# SCH_Nucleo__LCD__v5_2023-10-04.net
KiCad netlist of a schematic drawn in EasyEDA
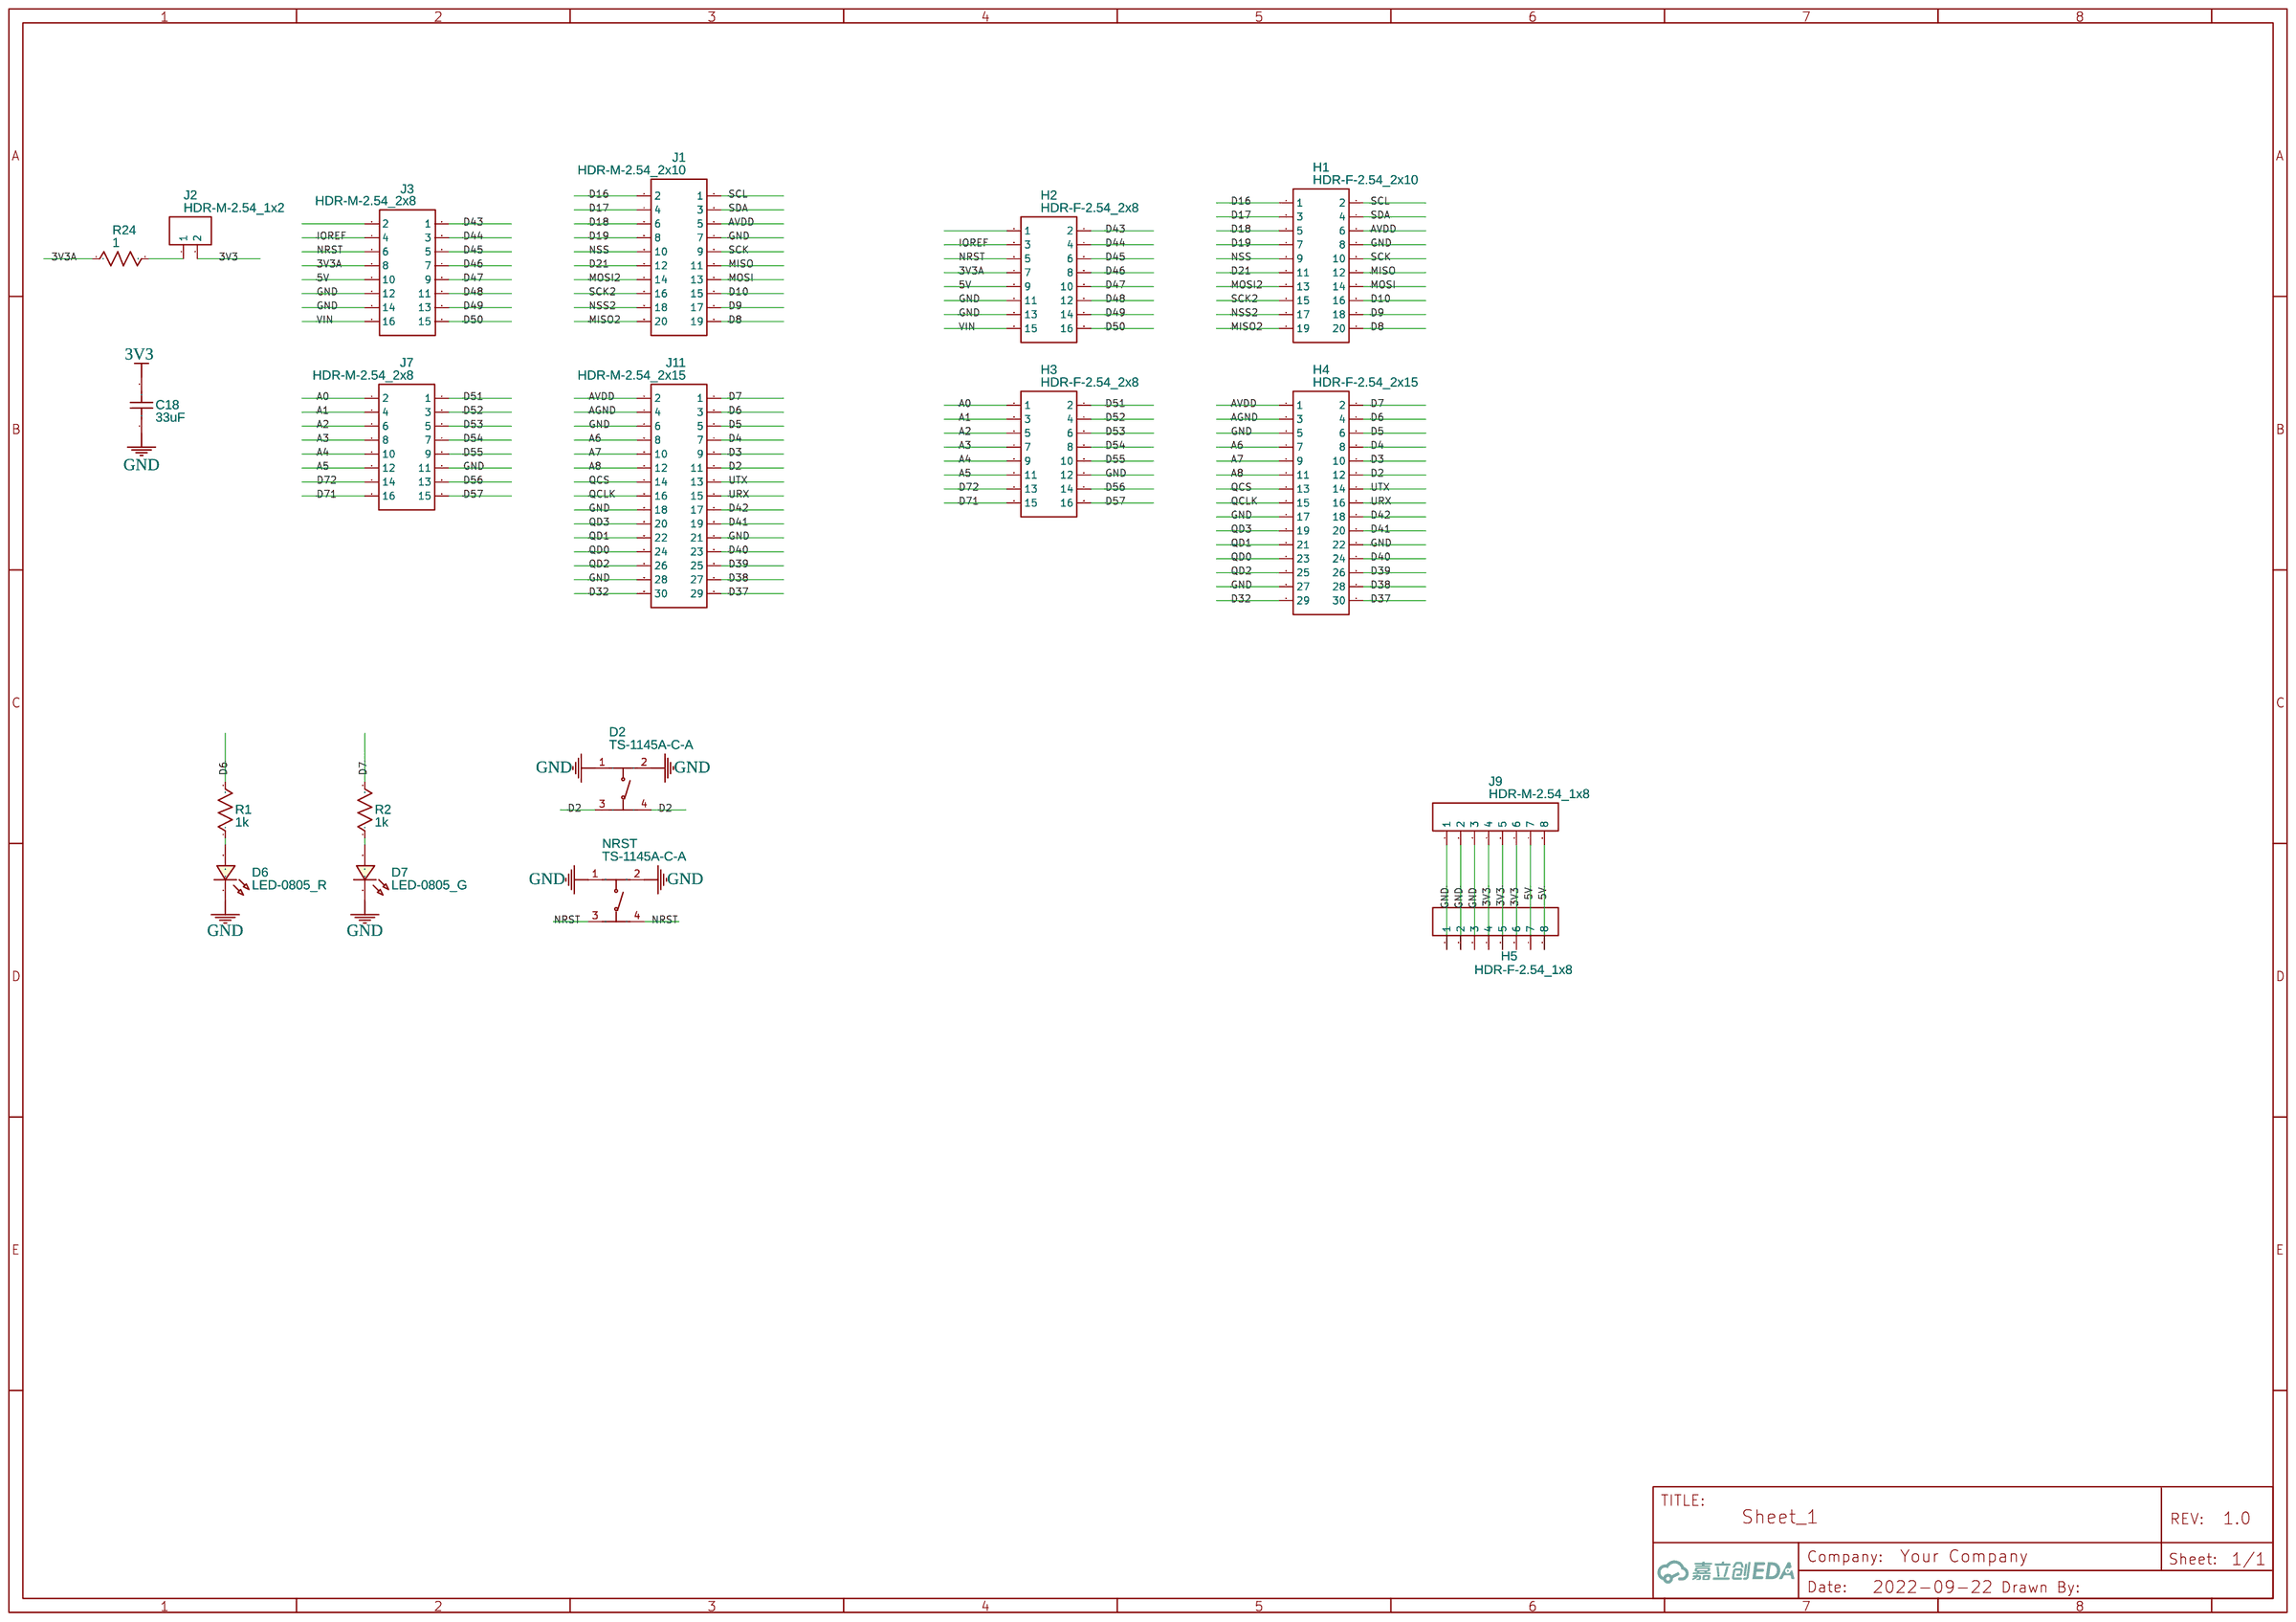
[diagram p0: 连接器]
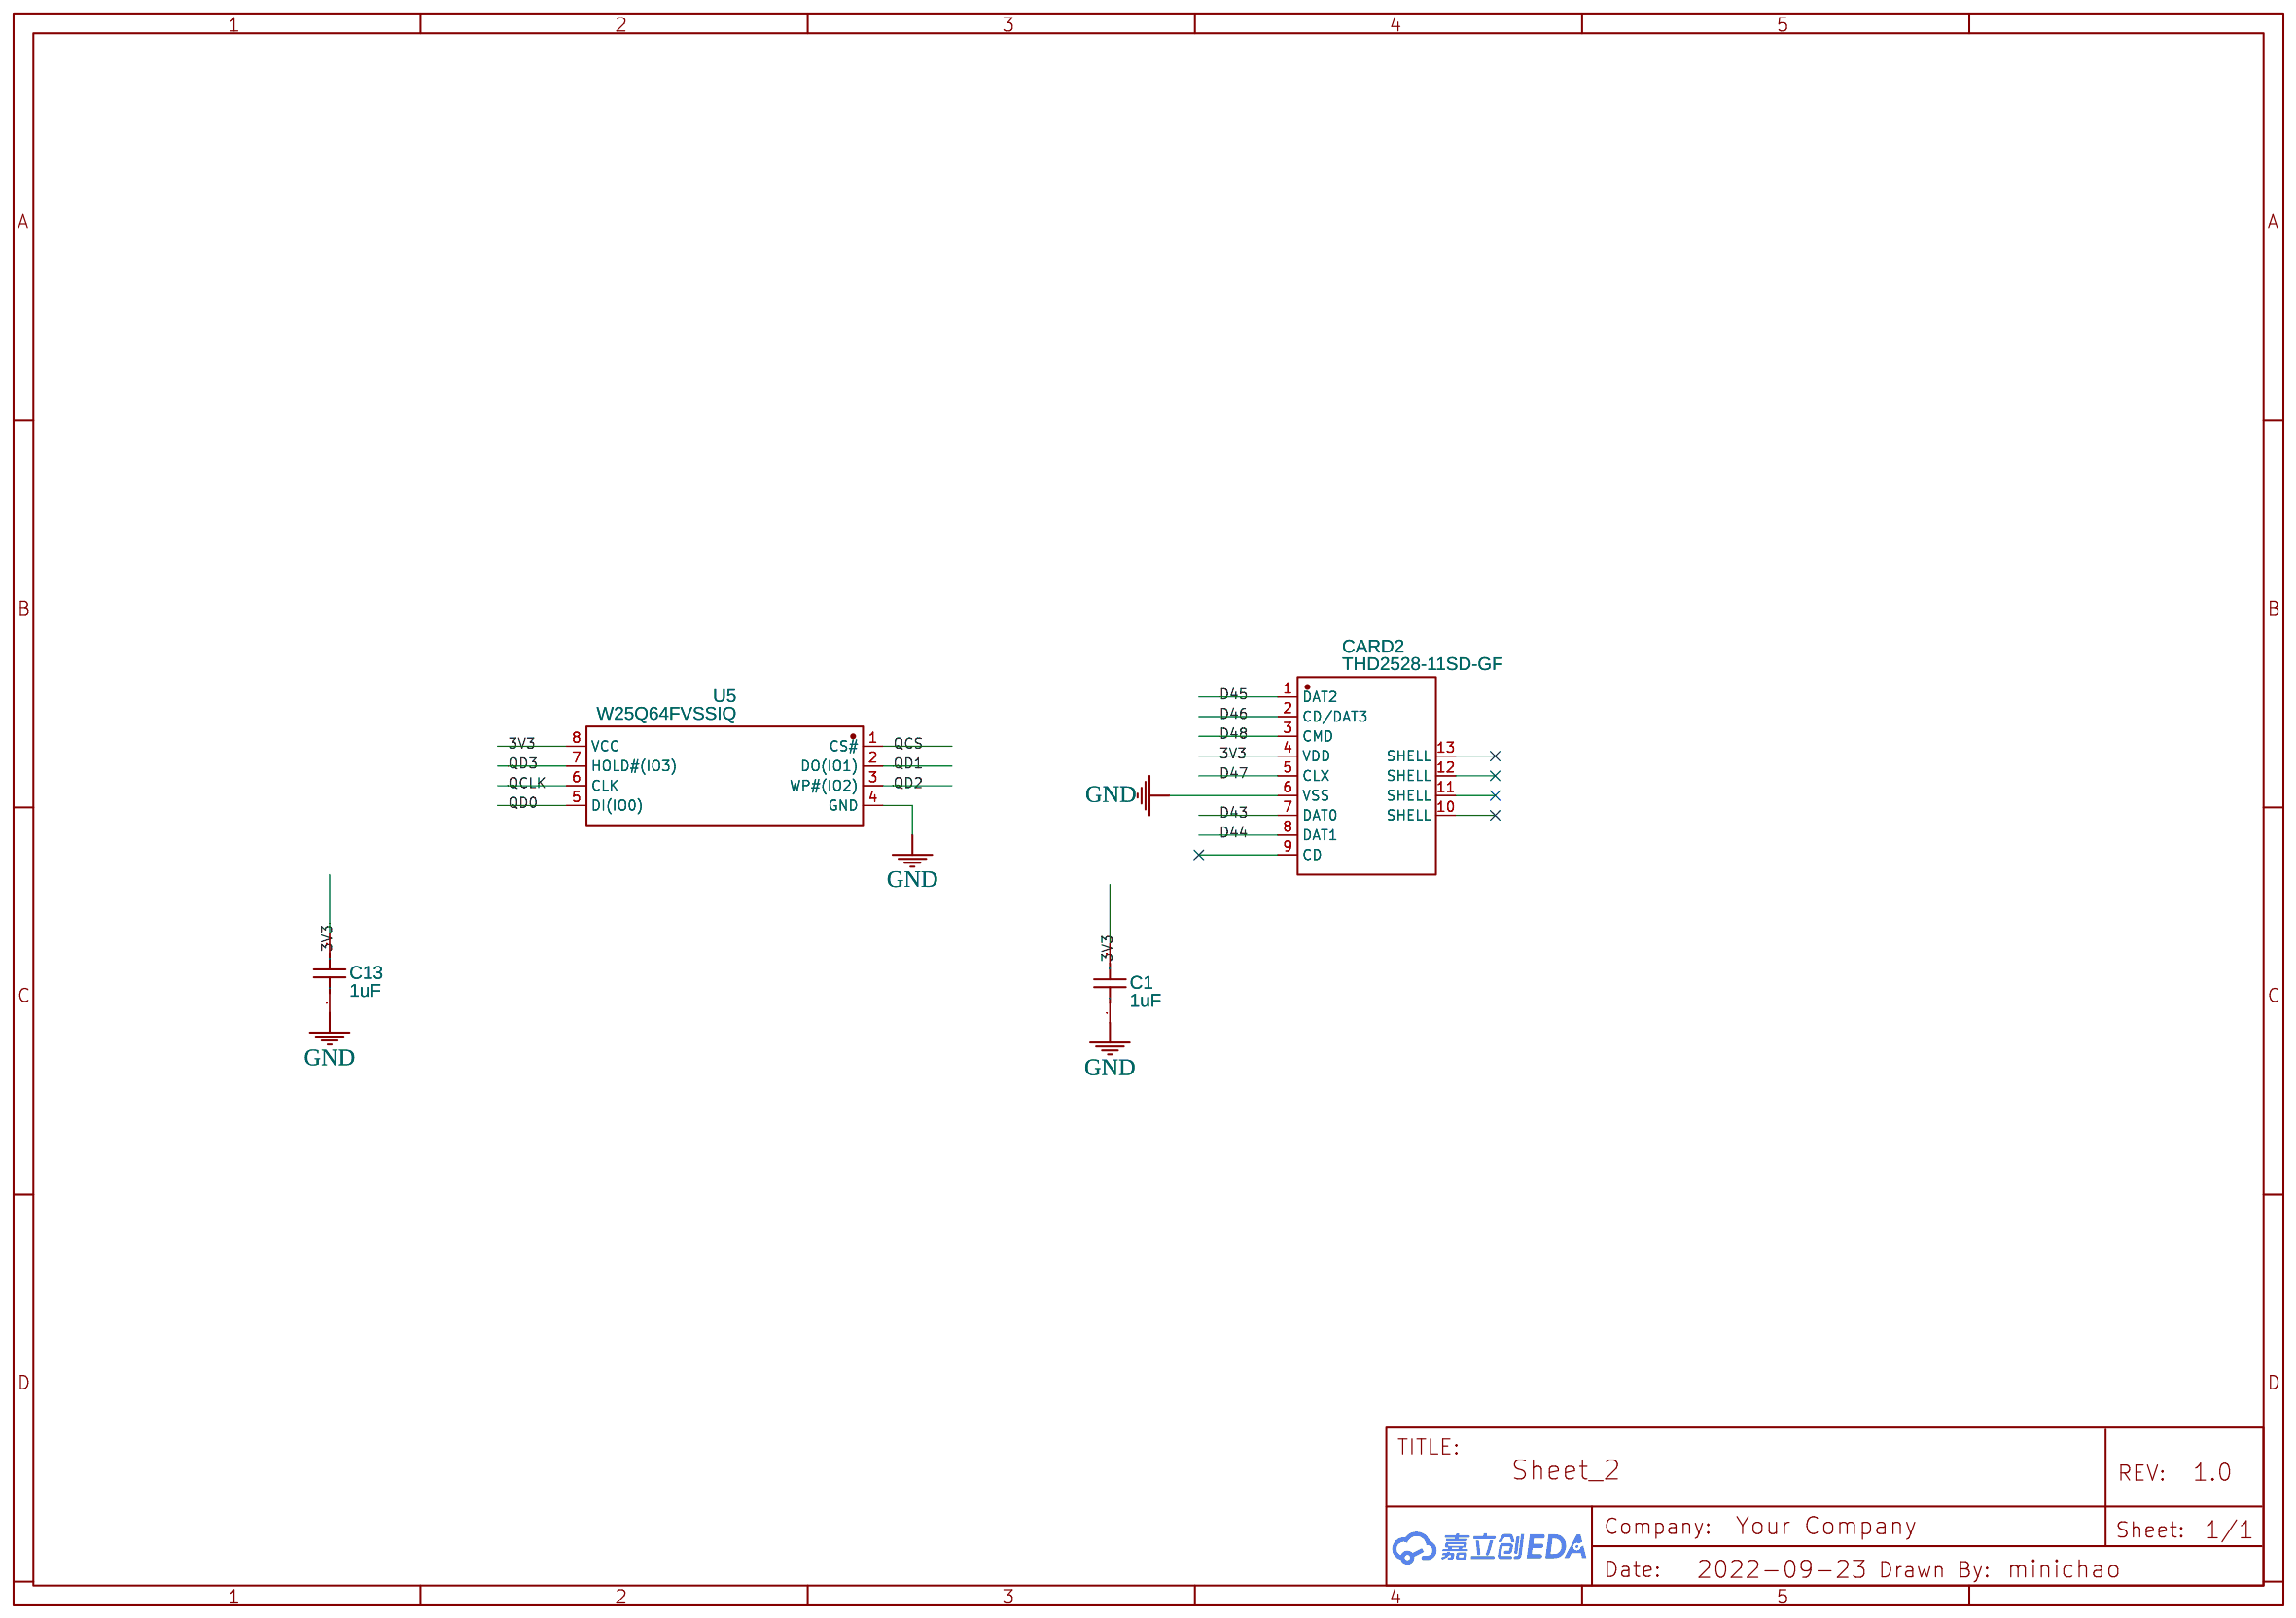
[diagram p1: 存储]
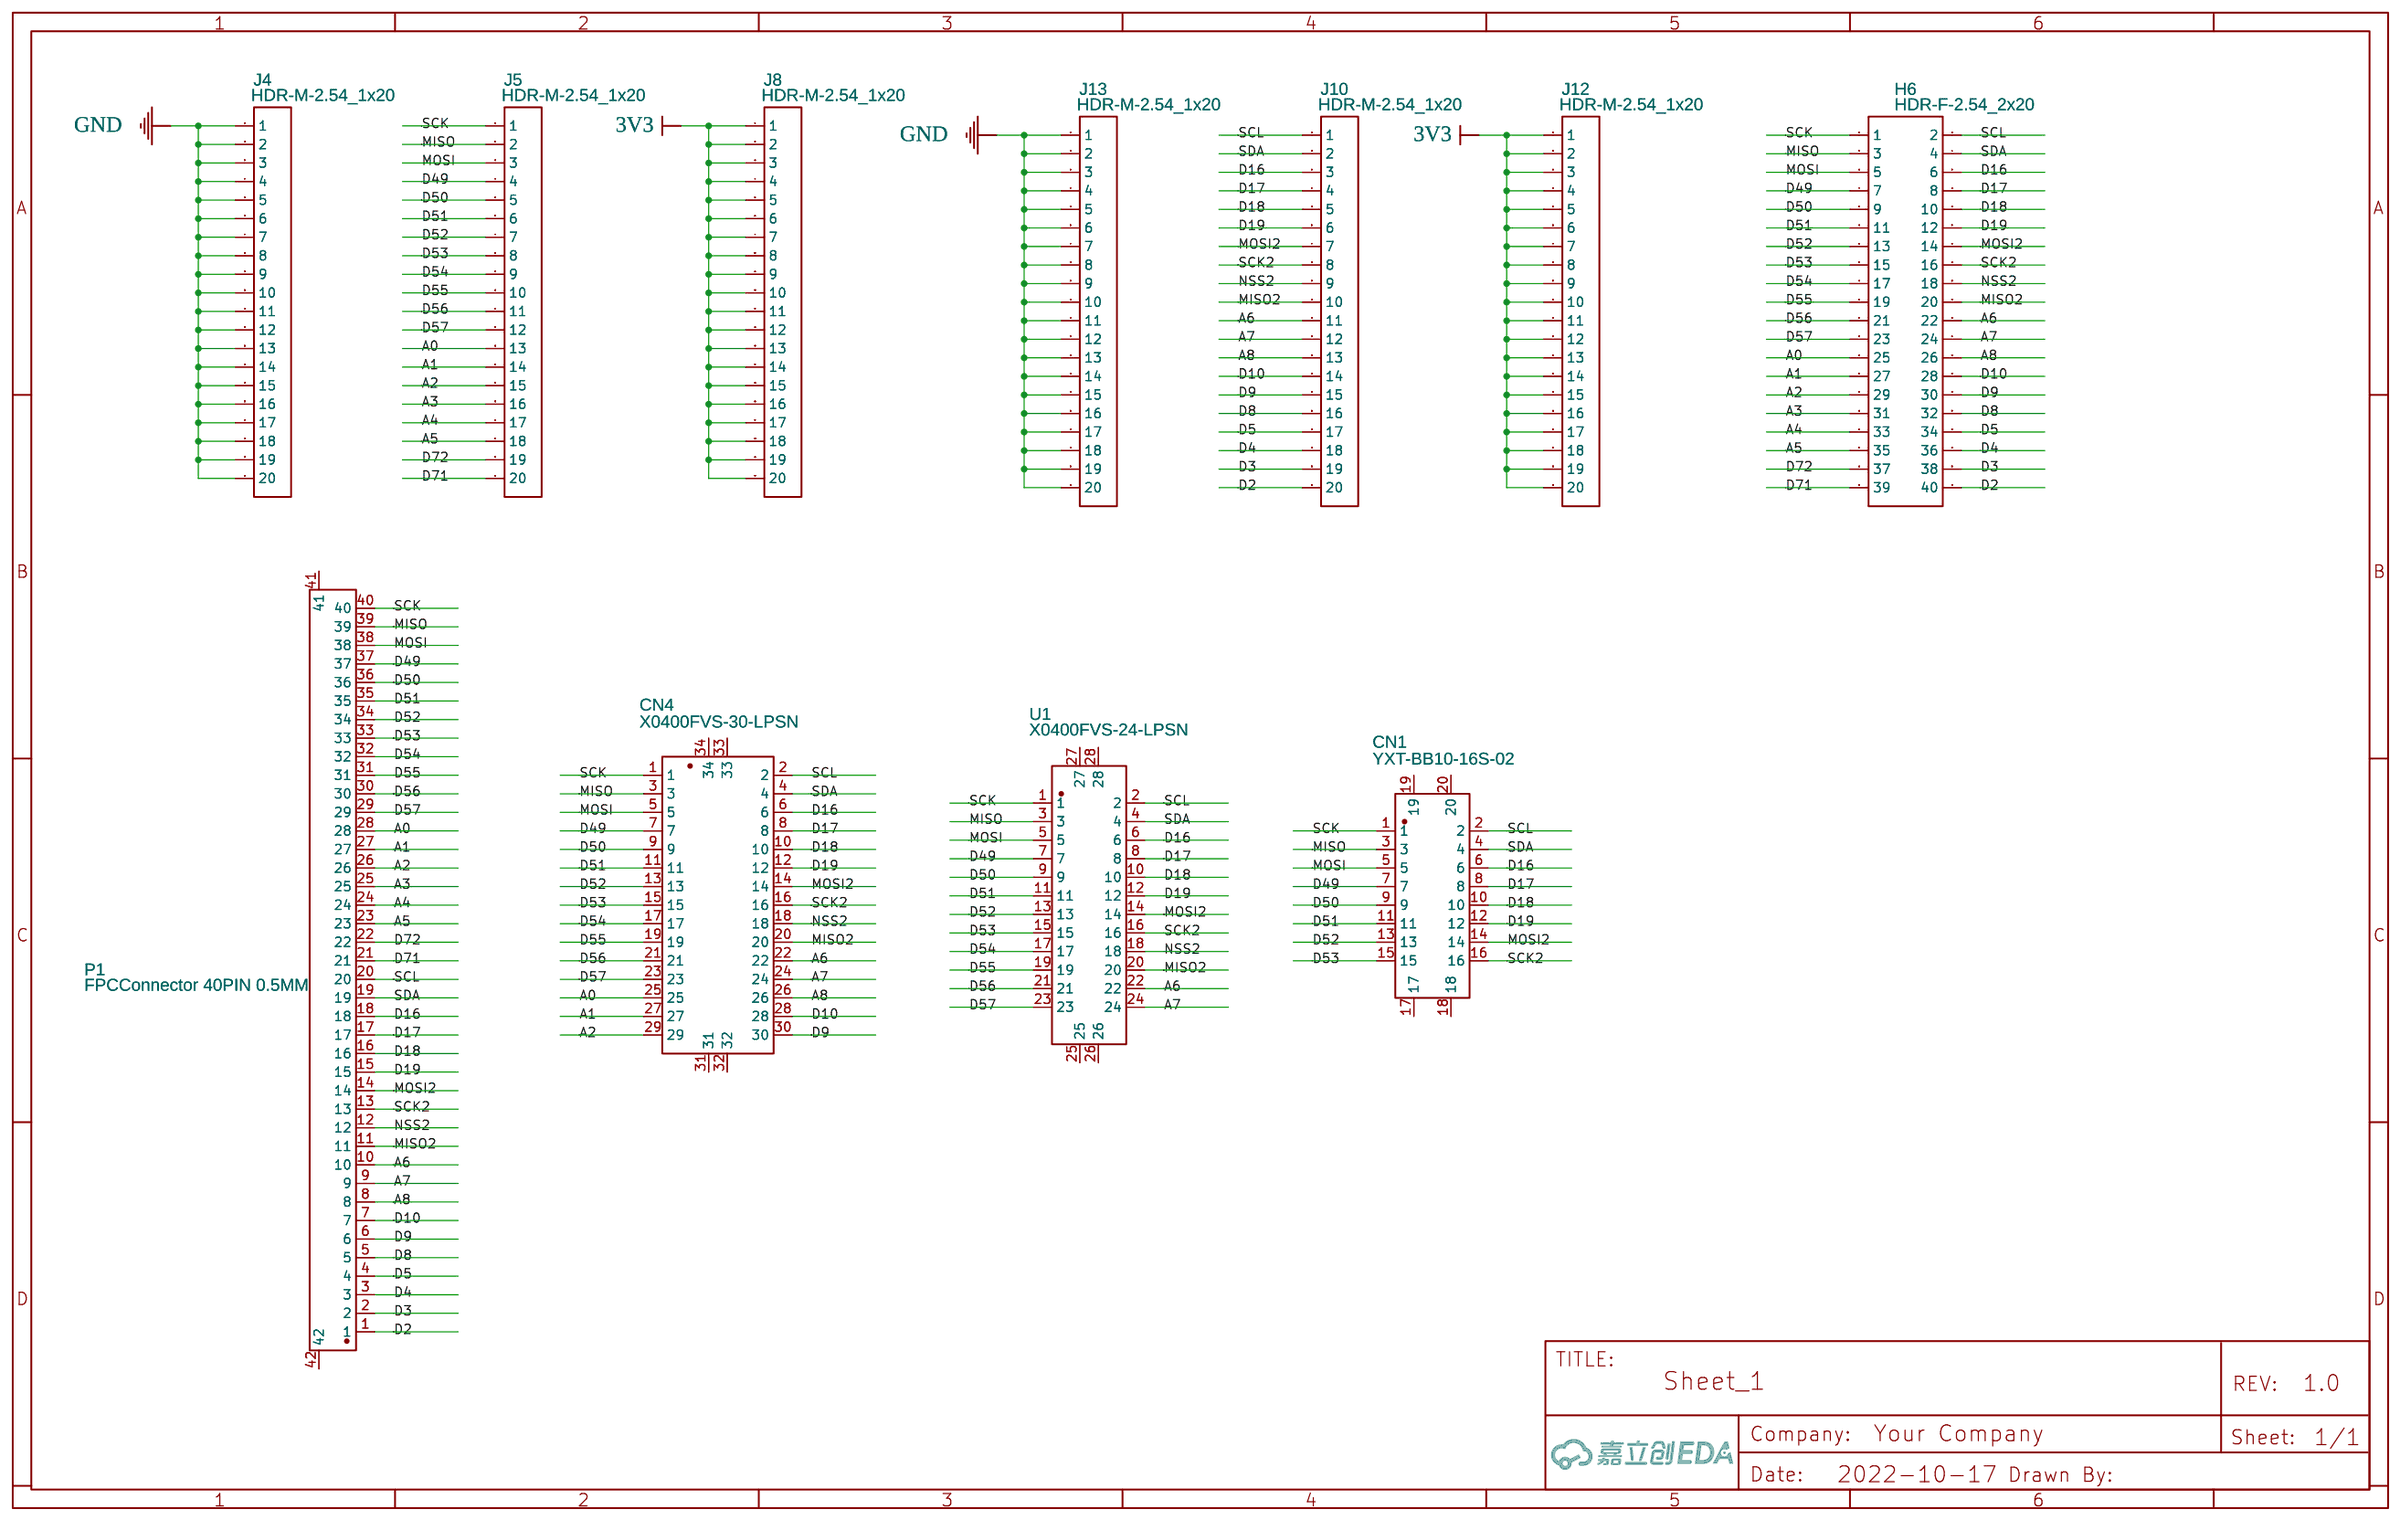
[diagram p2: 显示]

(export (version "E")
  (design (tool "Eeschema 10.0.6"))
  (components
    (comp (ref "C18")
      (value "33uF")
      (fields
        (field (name "BOM_Manufacturer Part") "C3225X5R0J336MT0A0N")
        (field (name "BOM_Supplier Part") "C695362")
      )
      (libsource (lib "") (part "C3225X5R0J336MT0A0N"))
    )
    (comp (ref "D2")
      (value "TS-1145A-C-A")
      (fields (field (name "BOM_Supplier Part") "C318903"))
      (libsource (lib "") (part "TS-1145A-C-A_1"))
    )
    (comp (ref "D6")
      (value "LED-0805_R")
      (fields
        (field (name "BOM_Manufacturer Part") "17-21SURC/S530-A3/TR8")
        (field (name "BOM_Supplier Part") "C72037")
      )
      (libsource (lib "") (part "LED-0805_R"))
    )
    (comp (ref "D7")
      (value "LED-0805_G")
      (fields (field (name "BOM_Manufacturer Part") "NCD0805G1") (field (name "BOM_Supplier Part") "C84260"))
      (libsource (lib "") (part "LED-0805_G"))
    )
    (comp (ref "H1")
      (value "HDR-F-2.54_2x10")
      (fields (field (name "BOM_Supplier Part") "C30867"))
      (libsource (lib "") (part "HDR-F-2.54_2x10"))
    )
    (comp (ref "H2")
      (value "HDR-F-2.54_2x8")
      (fields (field (name "BOM_Supplier Part") "C30734"))
      (libsource (lib "") (part "HDR-F-2.54_2x8"))
    )
    (comp (ref "H3")
      (value "HDR-F-2.54_2x8")
      (fields (field (name "BOM_Supplier Part") "C30734"))
      (libsource (lib "") (part "HDR-F-2.54_2x8"))
    )
    (comp (ref "H4")
      (value "HDR-F-2.54_2x15")
      (fields (field (name "BOM_Supplier Part") "C169818"))
      (libsource (lib "") (part "HDR-F-2.54_2x15"))
    )
    (comp (ref "H5")
      (value "HDR-F-2.54_1x8")
      (fields (field (name "BOM_Supplier Part") "C225505"))
      (libsource (lib "") (part "HDR-F-2.54_1x8"))
    )
    (comp (ref "J1")
      (value "HDR-M-2.54_2x10")
      (fields (field (name "BOM_Supplier Part") "C124359"))
      (libsource (lib "") (part "HDR-M-2.54_2x10"))
    )
    (comp (ref "J2")
      (value "HDR-M-2.54_1x2")
      (fields (field (name "BOM_Supplier Part") "C124375"))
      (libsource (lib "") (part "HDR-M-2.54_1x2"))
    )
    (comp (ref "J3")
      (value "HDR-M-2.54_2x8")
      (fields (field (name "BOM_Supplier Part") "C68234"))
      (libsource (lib "") (part "HDR-M-2.54_2x8"))
    )
    (comp (ref "J7")
      (value "HDR-M-2.54_2x8")
      (fields (field (name "BOM_Supplier Part") "C68234"))
      (libsource (lib "") (part "HDR-M-2.54_2x8_1"))
    )
    (comp (ref "J9")
      (value "HDR-M-2.54_1x8")
      (fields (field (name "BOM_Supplier Part") "C190820"))
      (libsource (lib "") (part "HDR-M-2.54_1x8"))
    )
    (comp (ref "J11")
      (value "HDR-M-2.54_2x15")
      (fields (field (name "BOM_Supplier Part") "C56496"))
      (libsource (lib "") (part "HDR-M-2.54_2x15"))
    )
    (comp (ref "NRST")
      (value "TS-1145A-C-A")
      (fields (field (name "BOM_Supplier Part") "C318903"))
      (libsource (lib "") (part "TS-1145A-C-A"))
    )
    (comp (ref "R1")
      (value "1k")
      (fields
        (field (name "BOM_Manufacturer Part") "TC0525F1001T5E")
        (field (name "BOM_Supplier Part") "C75781")
      )
      (libsource (lib "") (part "R_0805_US_1"))
    )
    (comp (ref "R2")
      (value "1k")
      (fields
        (field (name "BOM_Manufacturer Part") "TC0525F1001T5E")
        (field (name "BOM_Supplier Part") "C75781")
      )
      (libsource (lib "") (part "R_0805_US_1"))
    )
    (comp (ref "R24") (value "1") (libsource (lib "") (part "R_0805_US")))
    (comp (ref "C1")
      (value "1uF")
      (fields
        (field (name "BOM_Manufacturer Part") "0805B105M500NT")
        (field (name "BOM_Supplier Part") "C2913555")
      )
      (libsource (lib "") (part "C_0805_US"))
    )
    (comp (ref "C13")
      (value "1uF")
      (fields
        (field (name "BOM_Manufacturer Part") "0805B105M500NT")
        (field (name "BOM_Supplier Part") "C2913555")
      )
      (libsource (lib "") (part "C_0805_US"))
    )
    (comp (ref "CARD2")
      (value "THD2528-11SD-GF")
      (fields (field (name "BOM_Supplier Part") "C283232"))
      (libsource (lib "") (part "THD2528-11SD-GF"))
    )
    (comp (ref "U5")
      (value "W25Q64FVSSIQ")
      (fields (field (name "BOM_Supplier Part") "C2943203"))
      (libsource (lib "") (part "W25Q64FVSSIQ"))
    )
    (comp (ref "CN1")
      (value "YXT-BB10-16S-02")
      (fields (field (name "BOM_Supplier Part") "C2763964"))
      (libsource (lib "") (part "YXT-BB10-16S-02"))
    )
    (comp (ref "CN4")
      (value "X0400FVS-30-LPSN")
      (fields (field (name "BOM_Supplier Part") "C2880693"))
      (libsource (lib "") (part "X0400FVS-30-LPSN"))
    )
    (comp (ref "H6")
      (value "HDR-F-2.54_2x20")
      (fields (field (name "BOM_Supplier Part") "C50982"))
      (libsource (lib "") (part "HDR-F-2.54_2x20"))
    )
    (comp (ref "J4")
      (value "HDR-M-2.54_1x20")
      (fields (field (name "BOM_Supplier Part") "C50981"))
      (libsource (lib "") (part "HDR-M-2.54_1x20"))
    )
    (comp (ref "J5")
      (value "HDR-M-2.54_1x20")
      (fields (field (name "BOM_Supplier Part") "C50981"))
      (libsource (lib "") (part "HDR-M-2.54_1x20"))
    )
    (comp (ref "J8")
      (value "HDR-M-2.54_1x20")
      (fields (field (name "BOM_Supplier Part") "C50981"))
      (libsource (lib "") (part "HDR-M-2.54_1x20"))
    )
    (comp (ref "J10")
      (value "HDR-M-2.54_1x20")
      (fields (field (name "BOM_Supplier Part") "C50981"))
      (libsource (lib "") (part "HDR-M-2.54_1x20"))
    )
    (comp (ref "J12")
      (value "HDR-M-2.54_1x20")
      (fields (field (name "BOM_Supplier Part") "C50981"))
      (libsource (lib "") (part "HDR-M-2.54_1x20"))
    )
    (comp (ref "J13")
      (value "HDR-M-2.54_1x20")
      (fields (field (name "BOM_Supplier Part") "C50981"))
      (libsource (lib "") (part "HDR-M-2.54_1x20"))
    )
    (comp (ref "P1")
      (value "FPCConnector 40PIN 0.5MM")
      (fields (field (name "BOM_Manufacturer Part") "0.5-40P翻盖") (field (name "BOM_Supplier Part") "C9160"))
      (libsource (lib "") (part "FPCConnector 40PIN 0.5MM"))
    )
    (comp (ref "U1")
      (value "X0400FVS-24-LPSN")
      (fields (field (name "BOM_Supplier Part") "C2880692"))
      (libsource (lib "") (part "X0400FVS-24-LPSN"))
    )
  )
  (nets
    (net (code "1") (name "3V3") (class "Default")
      (node (ref "C1") (pin "2") (pinfunction "2_2") (pintype "unspecified"))
      (node (ref "C13") (pin "2") (pinfunction "2_2") (pintype "unspecified"))
      (node (ref "C18") (pin "2") (pinfunction "2_2") (pintype "unspecified"))
      (node (ref "CARD2") (pin "4") (pinfunction "VDD_4") (pintype "unspecified"))
      (node (ref "H5") (pin "4") (pinfunction "4_4") (pintype "unspecified"))
      (node (ref "H5") (pin "5") (pinfunction "5_5") (pintype "unspecified"))
      (node (ref "H5") (pin "6") (pinfunction "6_6") (pintype "unspecified"))
      (node (ref "J12") (pin "1") (pinfunction "1_1") (pintype "unspecified"))
      (node (ref "J12") (pin "10") (pinfunction "10_10") (pintype "unspecified"))
      (node (ref "J12") (pin "11") (pinfunction "11_11") (pintype "unspecified"))
      (node (ref "J12") (pin "12") (pinfunction "12_12") (pintype "unspecified"))
      (node (ref "J12") (pin "13") (pinfunction "13_13") (pintype "unspecified"))
      (node (ref "J12") (pin "14") (pinfunction "14_14") (pintype "unspecified"))
      (node (ref "J12") (pin "15") (pinfunction "15_15") (pintype "unspecified"))
      (node (ref "J12") (pin "16") (pinfunction "16_16") (pintype "unspecified"))
      (node (ref "J12") (pin "17") (pinfunction "17_17") (pintype "unspecified"))
      (node (ref "J12") (pin "18") (pinfunction "18_18") (pintype "unspecified"))
      (node (ref "J12") (pin "19") (pinfunction "19_19") (pintype "unspecified"))
      (node (ref "J12") (pin "2") (pinfunction "2_2") (pintype "unspecified"))
      (node (ref "J12") (pin "20") (pinfunction "20_20") (pintype "unspecified"))
      (node (ref "J12") (pin "3") (pinfunction "3_3") (pintype "unspecified"))
      (node (ref "J12") (pin "4") (pinfunction "4_4") (pintype "unspecified"))
      (node (ref "J12") (pin "5") (pinfunction "5_5") (pintype "unspecified"))
      (node (ref "J12") (pin "6") (pinfunction "6_6") (pintype "unspecified"))
      (node (ref "J12") (pin "7") (pinfunction "7_7") (pintype "unspecified"))
      (node (ref "J12") (pin "8") (pinfunction "8_8") (pintype "unspecified"))
      (node (ref "J12") (pin "9") (pinfunction "9_9") (pintype "unspecified"))
      (node (ref "J2") (pin "2") (pinfunction "2_2") (pintype "unspecified"))
      (node (ref "J8") (pin "1") (pinfunction "1_1") (pintype "unspecified"))
      (node (ref "J8") (pin "10") (pinfunction "10_10") (pintype "unspecified"))
      (node (ref "J8") (pin "11") (pinfunction "11_11") (pintype "unspecified"))
      (node (ref "J8") (pin "12") (pinfunction "12_12") (pintype "unspecified"))
      (node (ref "J8") (pin "13") (pinfunction "13_13") (pintype "unspecified"))
      (node (ref "J8") (pin "14") (pinfunction "14_14") (pintype "unspecified"))
      (node (ref "J8") (pin "15") (pinfunction "15_15") (pintype "unspecified"))
      (node (ref "J8") (pin "16") (pinfunction "16_16") (pintype "unspecified"))
      (node (ref "J8") (pin "17") (pinfunction "17_17") (pintype "unspecified"))
      (node (ref "J8") (pin "18") (pinfunction "18_18") (pintype "unspecified"))
      (node (ref "J8") (pin "19") (pinfunction "19_19") (pintype "unspecified"))
      (node (ref "J8") (pin "2") (pinfunction "2_2") (pintype "unspecified"))
      (node (ref "J8") (pin "20") (pinfunction "20_20") (pintype "unspecified"))
      (node (ref "J8") (pin "3") (pinfunction "3_3") (pintype "unspecified"))
      (node (ref "J8") (pin "4") (pinfunction "4_4") (pintype "unspecified"))
      (node (ref "J8") (pin "5") (pinfunction "5_5") (pintype "unspecified"))
      (node (ref "J8") (pin "6") (pinfunction "6_6") (pintype "unspecified"))
      (node (ref "J8") (pin "7") (pinfunction "7_7") (pintype "unspecified"))
      (node (ref "J8") (pin "8") (pinfunction "8_8") (pintype "unspecified"))
      (node (ref "J8") (pin "9") (pinfunction "9_9") (pintype "unspecified"))
      (node (ref "J9") (pin "4") (pinfunction "4_4") (pintype "unspecified"))
      (node (ref "J9") (pin "5") (pinfunction "5_5") (pintype "unspecified"))
      (node (ref "J9") (pin "6") (pinfunction "6_6") (pintype "unspecified"))
      (node (ref "U5") (pin "8") (pinfunction "VCC_8") (pintype "unspecified"))
    )
    (net (code "2") (name "3V3A") (class "Default")
      (node (ref "H2") (pin "7") (pinfunction "7_7") (pintype "input"))
      (node (ref "J3") (pin "8") (pinfunction "8_8") (pintype "input"))
      (node (ref "R24") (pin "1") (pinfunction "1_1") (pintype "unspecified"))
    )
    (net (code "3") (name "5V") (class "Default")
      (node (ref "H2") (pin "9") (pinfunction "9_9") (pintype "input"))
      (node (ref "H5") (pin "7") (pinfunction "7_7") (pintype "unspecified"))
      (node (ref "H5") (pin "8") (pinfunction "8_8") (pintype "unspecified"))
      (node (ref "J3") (pin "10") (pinfunction "10_10") (pintype "input"))
      (node (ref "J9") (pin "7") (pinfunction "7_7") (pintype "unspecified"))
      (node (ref "J9") (pin "8") (pinfunction "8_8") (pintype "unspecified"))
    )
    (net (code "4") (name "A0") (class "Default")
      (node (ref "CN4") (pin "25") (pinfunction "25_25") (pintype "unspecified"))
      (node (ref "H3") (pin "1") (pinfunction "1_1") (pintype "input"))
      (node (ref "H6") (pin "25") (pinfunction "25_25") (pintype "input"))
      (node (ref "J5") (pin "13") (pinfunction "13_13") (pintype "unspecified"))
      (node (ref "J7") (pin "2") (pinfunction "2_2") (pintype "input"))
      (node (ref "P1") (pin "28") (pinfunction "28_28") (pintype "unspecified"))
    )
    (net (code "5") (name "A1") (class "Default")
      (node (ref "CN4") (pin "27") (pinfunction "27_27") (pintype "unspecified"))
      (node (ref "H3") (pin "3") (pinfunction "3_3") (pintype "input"))
      (node (ref "H6") (pin "27") (pinfunction "27_27") (pintype "input"))
      (node (ref "J5") (pin "14") (pinfunction "14_14") (pintype "unspecified"))
      (node (ref "J7") (pin "4") (pinfunction "4_4") (pintype "input"))
      (node (ref "P1") (pin "27") (pinfunction "27_27") (pintype "unspecified"))
    )
    (net (code "6") (name "A2") (class "Default")
      (node (ref "CN4") (pin "29") (pinfunction "29_29") (pintype "unspecified"))
      (node (ref "H3") (pin "5") (pinfunction "5_5") (pintype "input"))
      (node (ref "H6") (pin "29") (pinfunction "29_29") (pintype "input"))
      (node (ref "J5") (pin "15") (pinfunction "15_15") (pintype "unspecified"))
      (node (ref "J7") (pin "6") (pinfunction "6_6") (pintype "input"))
      (node (ref "P1") (pin "26") (pinfunction "26_26") (pintype "unspecified"))
    )
    (net (code "7") (name "A3") (class "Default")
      (node (ref "H3") (pin "7") (pinfunction "7_7") (pintype "input"))
      (node (ref "H6") (pin "31") (pinfunction "31_31") (pintype "input"))
      (node (ref "J5") (pin "16") (pinfunction "16_16") (pintype "unspecified"))
      (node (ref "J7") (pin "8") (pinfunction "8_8") (pintype "input"))
      (node (ref "P1") (pin "25") (pinfunction "25_25") (pintype "unspecified"))
    )
    (net (code "8") (name "A4") (class "Default")
      (node (ref "H3") (pin "9") (pinfunction "9_9") (pintype "input"))
      (node (ref "H6") (pin "33") (pinfunction "33_33") (pintype "input"))
      (node (ref "J5") (pin "17") (pinfunction "17_17") (pintype "unspecified"))
      (node (ref "J7") (pin "10") (pinfunction "10_10") (pintype "input"))
      (node (ref "P1") (pin "24") (pinfunction "24_24") (pintype "unspecified"))
    )
    (net (code "9") (name "A5") (class "Default")
      (node (ref "H3") (pin "11") (pinfunction "11_11") (pintype "input"))
      (node (ref "H6") (pin "35") (pinfunction "35_35") (pintype "input"))
      (node (ref "J5") (pin "18") (pinfunction "18_18") (pintype "unspecified"))
      (node (ref "J7") (pin "12") (pinfunction "12_12") (pintype "input"))
      (node (ref "P1") (pin "23") (pinfunction "23_23") (pintype "unspecified"))
    )
    (net (code "10") (name "A6") (class "Default")
      (node (ref "CN4") (pin "22") (pinfunction "22_22") (pintype "unspecified"))
      (node (ref "H4") (pin "7") (pinfunction "7_7") (pintype "input"))
      (node (ref "H6") (pin "22") (pinfunction "22_22") (pintype "input"))
      (node (ref "J10") (pin "11") (pinfunction "11_11") (pintype "unspecified"))
      (node (ref "J11") (pin "8") (pinfunction "8_8") (pintype "input"))
      (node (ref "P1") (pin "10") (pinfunction "10_10") (pintype "unspecified"))
      (node (ref "U1") (pin "22") (pinfunction "22_22") (pintype "unspecified"))
    )
    (net (code "11") (name "A7") (class "Default")
      (node (ref "CN4") (pin "24") (pinfunction "24_24") (pintype "unspecified"))
      (node (ref "H4") (pin "9") (pinfunction "9_9") (pintype "input"))
      (node (ref "H6") (pin "24") (pinfunction "24_24") (pintype "input"))
      (node (ref "J10") (pin "12") (pinfunction "12_12") (pintype "unspecified"))
      (node (ref "J11") (pin "10") (pinfunction "10_10") (pintype "input"))
      (node (ref "P1") (pin "9") (pinfunction "9_9") (pintype "unspecified"))
      (node (ref "U1") (pin "24") (pinfunction "24_24") (pintype "unspecified"))
    )
    (net (code "12") (name "A8") (class "Default")
      (node (ref "CN4") (pin "26") (pinfunction "26_26") (pintype "unspecified"))
      (node (ref "H4") (pin "11") (pinfunction "11_11") (pintype "input"))
      (node (ref "H6") (pin "26") (pinfunction "26_26") (pintype "input"))
      (node (ref "J10") (pin "13") (pinfunction "13_13") (pintype "unspecified"))
      (node (ref "J11") (pin "12") (pinfunction "12_12") (pintype "input"))
      (node (ref "P1") (pin "8") (pinfunction "8_8") (pintype "unspecified"))
    )
    (net (code "13") (name "AGND") (class "Default")
      (node (ref "H4") (pin "3") (pinfunction "3_3") (pintype "input"))
      (node (ref "J11") (pin "4") (pinfunction "4_4") (pintype "input"))
    )
    (net (code "14") (name "AVDD") (class "Default")
      (node (ref "H1") (pin "6") (pinfunction "6_6") (pintype "input"))
      (node (ref "H4") (pin "1") (pinfunction "1_1") (pintype "input"))
      (node (ref "J1") (pin "5") (pinfunction "5_5") (pintype "unspecified"))
      (node (ref "J11") (pin "2") (pinfunction "2_2") (pintype "input"))
    )
    (net (code "15") (name "D2") (class "Default")
      (node (ref "D2") (pin "3") (pinfunction "3_3") (pintype "unspecified"))
      (node (ref "D2") (pin "4") (pinfunction "4_4") (pintype "unspecified"))
      (node (ref "H4") (pin "12") (pinfunction "12_12") (pintype "input"))
      (node (ref "H6") (pin "40") (pinfunction "40_40") (pintype "input"))
      (node (ref "J10") (pin "20") (pinfunction "20_20") (pintype "unspecified"))
      (node (ref "J11") (pin "11") (pinfunction "11_11") (pintype "input"))
      (node (ref "P1") (pin "1") (pinfunction "1_1") (pintype "unspecified"))
    )
    (net (code "16") (name "D3") (class "Default")
      (node (ref "H4") (pin "10") (pinfunction "10_10") (pintype "input"))
      (node (ref "H6") (pin "38") (pinfunction "38_38") (pintype "input"))
      (node (ref "J10") (pin "19") (pinfunction "19_19") (pintype "unspecified"))
      (node (ref "J11") (pin "9") (pinfunction "9_9") (pintype "input"))
      (node (ref "P1") (pin "2") (pinfunction "2_2") (pintype "unspecified"))
    )
    (net (code "17") (name "D4") (class "Default")
      (node (ref "H4") (pin "8") (pinfunction "8_8") (pintype "input"))
      (node (ref "H6") (pin "36") (pinfunction "36_36") (pintype "input"))
      (node (ref "J10") (pin "18") (pinfunction "18_18") (pintype "unspecified"))
      (node (ref "J11") (pin "7") (pinfunction "7_7") (pintype "input"))
      (node (ref "P1") (pin "3") (pinfunction "3_3") (pintype "unspecified"))
    )
    (net (code "18") (name "D5") (class "Default")
      (node (ref "H4") (pin "6") (pinfunction "6_6") (pintype "input"))
      (node (ref "H6") (pin "34") (pinfunction "34_34") (pintype "input"))
      (node (ref "J10") (pin "17") (pinfunction "17_17") (pintype "unspecified"))
      (node (ref "J11") (pin "5") (pinfunction "5_5") (pintype "input"))
      (node (ref "P1") (pin "4") (pinfunction "4_4") (pintype "unspecified"))
    )
    (net (code "19") (name "D6") (class "Default")
      (node (ref "H4") (pin "4") (pinfunction "4_4") (pintype "input"))
      (node (ref "J11") (pin "3") (pinfunction "3_3") (pintype "input"))
      (node (ref "R1") (pin "2") (pinfunction "2_2") (pintype "unspecified"))
    )
    (net (code "20") (name "D7") (class "Default")
      (node (ref "H4") (pin "2") (pinfunction "2_2") (pintype "input"))
      (node (ref "J11") (pin "1") (pinfunction "1_1") (pintype "input"))
      (node (ref "R2") (pin "2") (pinfunction "2_2") (pintype "unspecified"))
    )
    (net (code "21") (name "D8") (class "Default")
      (node (ref "H1") (pin "20") (pinfunction "20_20") (pintype "input"))
      (node (ref "H6") (pin "32") (pinfunction "32_32") (pintype "input"))
      (node (ref "J1") (pin "19") (pinfunction "19_19") (pintype "unspecified"))
      (node (ref "J10") (pin "16") (pinfunction "16_16") (pintype "unspecified"))
      (node (ref "P1") (pin "5") (pinfunction "5_5") (pintype "unspecified"))
    )
    (net (code "22") (name "D9") (class "Default")
      (node (ref "CN4") (pin "30") (pinfunction "30_30") (pintype "unspecified"))
      (node (ref "H1") (pin "18") (pinfunction "18_18") (pintype "input"))
      (node (ref "H6") (pin "30") (pinfunction "30_30") (pintype "input"))
      (node (ref "J1") (pin "17") (pinfunction "17_17") (pintype "unspecified"))
      (node (ref "J10") (pin "15") (pinfunction "15_15") (pintype "unspecified"))
      (node (ref "P1") (pin "6") (pinfunction "6_6") (pintype "unspecified"))
    )
    (net (code "23") (name "D10") (class "Default")
      (node (ref "CN4") (pin "28") (pinfunction "28_28") (pintype "unspecified"))
      (node (ref "H1") (pin "16") (pinfunction "16_16") (pintype "input"))
      (node (ref "H6") (pin "28") (pinfunction "28_28") (pintype "input"))
      (node (ref "J1") (pin "15") (pinfunction "15_15") (pintype "unspecified"))
      (node (ref "J10") (pin "14") (pinfunction "14_14") (pintype "unspecified"))
      (node (ref "P1") (pin "7") (pinfunction "7_7") (pintype "unspecified"))
    )
    (net (code "24") (name "D16") (class "Default")
      (node (ref "CN1") (pin "6") (pinfunction "6_6") (pintype "unspecified"))
      (node (ref "CN4") (pin "6") (pinfunction "6_6") (pintype "unspecified"))
      (node (ref "H1") (pin "1") (pinfunction "1_1") (pintype "input"))
      (node (ref "H6") (pin "6") (pinfunction "6_6") (pintype "input"))
      (node (ref "J1") (pin "2") (pinfunction "2_2") (pintype "unspecified"))
      (node (ref "J10") (pin "3") (pinfunction "3_3") (pintype "unspecified"))
      (node (ref "P1") (pin "18") (pinfunction "18_18") (pintype "unspecified"))
      (node (ref "U1") (pin "6") (pinfunction "6_6") (pintype "unspecified"))
    )
    (net (code "25") (name "D17") (class "Default")
      (node (ref "CN1") (pin "8") (pinfunction "8_8") (pintype "unspecified"))
      (node (ref "CN4") (pin "8") (pinfunction "8_8") (pintype "unspecified"))
      (node (ref "H1") (pin "3") (pinfunction "3_3") (pintype "input"))
      (node (ref "H6") (pin "8") (pinfunction "8_8") (pintype "input"))
      (node (ref "J1") (pin "4") (pinfunction "4_4") (pintype "unspecified"))
      (node (ref "J10") (pin "4") (pinfunction "4_4") (pintype "unspecified"))
      (node (ref "P1") (pin "17") (pinfunction "17_17") (pintype "unspecified"))
      (node (ref "U1") (pin "8") (pinfunction "8_8") (pintype "unspecified"))
    )
    (net (code "26") (name "D18") (class "Default")
      (node (ref "CN1") (pin "10") (pinfunction "10_10") (pintype "unspecified"))
      (node (ref "CN4") (pin "10") (pinfunction "10_10") (pintype "unspecified"))
      (node (ref "H1") (pin "5") (pinfunction "5_5") (pintype "input"))
      (node (ref "H6") (pin "10") (pinfunction "10_10") (pintype "input"))
      (node (ref "J1") (pin "6") (pinfunction "6_6") (pintype "unspecified"))
      (node (ref "J10") (pin "5") (pinfunction "5_5") (pintype "unspecified"))
      (node (ref "P1") (pin "16") (pinfunction "16_16") (pintype "unspecified"))
      (node (ref "U1") (pin "10") (pinfunction "10_10") (pintype "unspecified"))
    )
    (net (code "27") (name "D19") (class "Default")
      (node (ref "CN1") (pin "12") (pinfunction "12_12") (pintype "unspecified"))
      (node (ref "CN4") (pin "12") (pinfunction "12_12") (pintype "unspecified"))
      (node (ref "H1") (pin "7") (pinfunction "7_7") (pintype "input"))
      (node (ref "H6") (pin "12") (pinfunction "12_12") (pintype "input"))
      (node (ref "J1") (pin "8") (pinfunction "8_8") (pintype "unspecified"))
      (node (ref "J10") (pin "6") (pinfunction "6_6") (pintype "unspecified"))
      (node (ref "P1") (pin "15") (pinfunction "15_15") (pintype "unspecified"))
      (node (ref "U1") (pin "12") (pinfunction "12_12") (pintype "unspecified"))
    )
    (net (code "28") (name "D21") (class "Default")
      (node (ref "H1") (pin "11") (pinfunction "11_11") (pintype "input"))
      (node (ref "J1") (pin "12") (pinfunction "12_12") (pintype "unspecified"))
    )
    (net (code "29") (name "D32") (class "Default")
      (node (ref "H4") (pin "29") (pinfunction "29_29") (pintype "input"))
      (node (ref "J11") (pin "30") (pinfunction "30_30") (pintype "input"))
    )
    (net (code "30") (name "D37") (class "Default")
      (node (ref "H4") (pin "30") (pinfunction "30_30") (pintype "input"))
      (node (ref "J11") (pin "29") (pinfunction "29_29") (pintype "input"))
    )
    (net (code "31") (name "D38") (class "Default")
      (node (ref "H4") (pin "28") (pinfunction "28_28") (pintype "input"))
      (node (ref "J11") (pin "27") (pinfunction "27_27") (pintype "input"))
    )
    (net (code "32") (name "D39") (class "Default")
      (node (ref "H4") (pin "26") (pinfunction "26_26") (pintype "input"))
      (node (ref "J11") (pin "25") (pinfunction "25_25") (pintype "input"))
    )
    (net (code "33") (name "D40") (class "Default")
      (node (ref "H4") (pin "24") (pinfunction "24_24") (pintype "input"))
      (node (ref "J11") (pin "23") (pinfunction "23_23") (pintype "input"))
    )
    (net (code "34") (name "D41") (class "Default")
      (node (ref "H4") (pin "20") (pinfunction "20_20") (pintype "input"))
      (node (ref "J11") (pin "19") (pinfunction "19_19") (pintype "input"))
    )
    (net (code "35") (name "D42") (class "Default")
      (node (ref "H4") (pin "18") (pinfunction "18_18") (pintype "input"))
      (node (ref "J11") (pin "17") (pinfunction "17_17") (pintype "input"))
    )
    (net (code "36") (name "D43") (class "Default")
      (node (ref "CARD2") (pin "7") (pinfunction "DAT0_7") (pintype "unspecified"))
      (node (ref "H2") (pin "2") (pinfunction "2_2") (pintype "input"))
      (node (ref "J3") (pin "1") (pinfunction "1_1") (pintype "input"))
    )
    (net (code "37") (name "D44") (class "Default")
      (node (ref "CARD2") (pin "8") (pinfunction "DAT1_8") (pintype "unspecified"))
      (node (ref "H2") (pin "4") (pinfunction "4_4") (pintype "input"))
      (node (ref "J3") (pin "3") (pinfunction "3_3") (pintype "input"))
    )
    (net (code "38") (name "D45") (class "Default")
      (node (ref "CARD2") (pin "1") (pinfunction "DAT2_1") (pintype "unspecified"))
      (node (ref "H2") (pin "6") (pinfunction "6_6") (pintype "input"))
      (node (ref "J3") (pin "5") (pinfunction "5_5") (pintype "input"))
    )
    (net (code "39") (name "D46") (class "Default")
      (node (ref "CARD2") (pin "2") (pinfunction "CD/DAT3_2") (pintype "unspecified"))
      (node (ref "H2") (pin "8") (pinfunction "8_8") (pintype "input"))
      (node (ref "J3") (pin "7") (pinfunction "7_7") (pintype "input"))
    )
    (net (code "40") (name "D47") (class "Default")
      (node (ref "CARD2") (pin "5") (pinfunction "CLX_5") (pintype "unspecified"))
      (node (ref "H2") (pin "10") (pinfunction "10_10") (pintype "input"))
      (node (ref "J3") (pin "9") (pinfunction "9_9") (pintype "input"))
    )
    (net (code "41") (name "D48") (class "Default")
      (node (ref "CARD2") (pin "3") (pinfunction "CMD_3") (pintype "unspecified"))
      (node (ref "H2") (pin "12") (pinfunction "12_12") (pintype "input"))
      (node (ref "J3") (pin "11") (pinfunction "11_11") (pintype "input"))
    )
    (net (code "42") (name "D49") (class "Default")
      (node (ref "CN1") (pin "7") (pinfunction "7_7") (pintype "unspecified"))
      (node (ref "CN4") (pin "7") (pinfunction "7_7") (pintype "unspecified"))
      (node (ref "H2") (pin "14") (pinfunction "14_14") (pintype "input"))
      (node (ref "H6") (pin "7") (pinfunction "7_7") (pintype "input"))
      (node (ref "J3") (pin "13") (pinfunction "13_13") (pintype "input"))
      (node (ref "J5") (pin "4") (pinfunction "4_4") (pintype "unspecified"))
      (node (ref "P1") (pin "37") (pinfunction "37_37") (pintype "unspecified"))
      (node (ref "U1") (pin "7") (pinfunction "7_7") (pintype "unspecified"))
    )
    (net (code "43") (name "D50") (class "Default")
      (node (ref "CN1") (pin "9") (pinfunction "9_9") (pintype "unspecified"))
      (node (ref "CN4") (pin "9") (pinfunction "9_9") (pintype "unspecified"))
      (node (ref "H2") (pin "16") (pinfunction "16_16") (pintype "input"))
      (node (ref "H6") (pin "9") (pinfunction "9_9") (pintype "input"))
      (node (ref "J3") (pin "15") (pinfunction "15_15") (pintype "input"))
      (node (ref "J5") (pin "5") (pinfunction "5_5") (pintype "unspecified"))
      (node (ref "P1") (pin "36") (pinfunction "36_36") (pintype "unspecified"))
      (node (ref "U1") (pin "9") (pinfunction "9_9") (pintype "unspecified"))
    )
    (net (code "44") (name "D51") (class "Default")
      (node (ref "CN1") (pin "11") (pinfunction "11_11") (pintype "unspecified"))
      (node (ref "CN4") (pin "11") (pinfunction "11_11") (pintype "unspecified"))
      (node (ref "H3") (pin "2") (pinfunction "2_2") (pintype "input"))
      (node (ref "H6") (pin "11") (pinfunction "11_11") (pintype "input"))
      (node (ref "J5") (pin "6") (pinfunction "6_6") (pintype "unspecified"))
      (node (ref "J7") (pin "1") (pinfunction "1_1") (pintype "input"))
      (node (ref "P1") (pin "35") (pinfunction "35_35") (pintype "unspecified"))
      (node (ref "U1") (pin "11") (pinfunction "11_11") (pintype "unspecified"))
    )
    (net (code "45") (name "D52") (class "Default")
      (node (ref "CN1") (pin "13") (pinfunction "13_13") (pintype "unspecified"))
      (node (ref "CN4") (pin "13") (pinfunction "13_13") (pintype "unspecified"))
      (node (ref "H3") (pin "4") (pinfunction "4_4") (pintype "input"))
      (node (ref "H6") (pin "13") (pinfunction "13_13") (pintype "input"))
      (node (ref "J5") (pin "7") (pinfunction "7_7") (pintype "unspecified"))
      (node (ref "J7") (pin "3") (pinfunction "3_3") (pintype "input"))
      (node (ref "P1") (pin "34") (pinfunction "34_34") (pintype "unspecified"))
      (node (ref "U1") (pin "13") (pinfunction "13_13") (pintype "unspecified"))
    )
    (net (code "46") (name "D53") (class "Default")
      (node (ref "CN1") (pin "15") (pinfunction "15_15") (pintype "unspecified"))
      (node (ref "CN4") (pin "15") (pinfunction "15_15") (pintype "unspecified"))
      (node (ref "H3") (pin "6") (pinfunction "6_6") (pintype "input"))
      (node (ref "H6") (pin "15") (pinfunction "15_15") (pintype "input"))
      (node (ref "J5") (pin "8") (pinfunction "8_8") (pintype "unspecified"))
      (node (ref "J7") (pin "5") (pinfunction "5_5") (pintype "input"))
      (node (ref "P1") (pin "33") (pinfunction "33_33") (pintype "unspecified"))
      (node (ref "U1") (pin "15") (pinfunction "15_15") (pintype "unspecified"))
    )
    (net (code "47") (name "D54") (class "Default")
      (node (ref "CN4") (pin "17") (pinfunction "17_17") (pintype "unspecified"))
      (node (ref "H3") (pin "8") (pinfunction "8_8") (pintype "input"))
      (node (ref "H6") (pin "17") (pinfunction "17_17") (pintype "input"))
      (node (ref "J5") (pin "9") (pinfunction "9_9") (pintype "unspecified"))
      (node (ref "J7") (pin "7") (pinfunction "7_7") (pintype "input"))
      (node (ref "P1") (pin "32") (pinfunction "32_32") (pintype "unspecified"))
      (node (ref "U1") (pin "17") (pinfunction "17_17") (pintype "unspecified"))
    )
    (net (code "48") (name "D55") (class "Default")
      (node (ref "CN4") (pin "19") (pinfunction "19_19") (pintype "unspecified"))
      (node (ref "H3") (pin "10") (pinfunction "10_10") (pintype "input"))
      (node (ref "H6") (pin "19") (pinfunction "19_19") (pintype "input"))
      (node (ref "J5") (pin "10") (pinfunction "10_10") (pintype "unspecified"))
      (node (ref "J7") (pin "9") (pinfunction "9_9") (pintype "input"))
      (node (ref "P1") (pin "31") (pinfunction "31_31") (pintype "unspecified"))
      (node (ref "U1") (pin "19") (pinfunction "19_19") (pintype "unspecified"))
    )
    (net (code "49") (name "D56") (class "Default")
      (node (ref "CN4") (pin "21") (pinfunction "21_21") (pintype "unspecified"))
      (node (ref "H3") (pin "14") (pinfunction "14_14") (pintype "input"))
      (node (ref "H6") (pin "21") (pinfunction "21_21") (pintype "input"))
      (node (ref "J5") (pin "11") (pinfunction "11_11") (pintype "unspecified"))
      (node (ref "J7") (pin "13") (pinfunction "13_13") (pintype "input"))
      (node (ref "P1") (pin "30") (pinfunction "30_30") (pintype "unspecified"))
      (node (ref "U1") (pin "21") (pinfunction "21_21") (pintype "unspecified"))
    )
    (net (code "50") (name "D57") (class "Default")
      (node (ref "CN4") (pin "23") (pinfunction "23_23") (pintype "unspecified"))
      (node (ref "H3") (pin "16") (pinfunction "16_16") (pintype "input"))
      (node (ref "H6") (pin "23") (pinfunction "23_23") (pintype "input"))
      (node (ref "J5") (pin "12") (pinfunction "12_12") (pintype "unspecified"))
      (node (ref "J7") (pin "15") (pinfunction "15_15") (pintype "input"))
      (node (ref "P1") (pin "29") (pinfunction "29_29") (pintype "unspecified"))
      (node (ref "U1") (pin "23") (pinfunction "23_23") (pintype "unspecified"))
    )
    (net (code "51") (name "D71") (class "Default")
      (node (ref "H3") (pin "15") (pinfunction "15_15") (pintype "input"))
      (node (ref "H6") (pin "39") (pinfunction "39_39") (pintype "input"))
      (node (ref "J5") (pin "20") (pinfunction "20_20") (pintype "unspecified"))
      (node (ref "J7") (pin "16") (pinfunction "16_16") (pintype "input"))
      (node (ref "P1") (pin "21") (pinfunction "21_21") (pintype "unspecified"))
    )
    (net (code "52") (name "D72") (class "Default")
      (node (ref "H3") (pin "13") (pinfunction "13_13") (pintype "input"))
      (node (ref "H6") (pin "37") (pinfunction "37_37") (pintype "input"))
      (node (ref "J5") (pin "19") (pinfunction "19_19") (pintype "unspecified"))
      (node (ref "J7") (pin "14") (pinfunction "14_14") (pintype "input"))
      (node (ref "P1") (pin "22") (pinfunction "22_22") (pintype "unspecified"))
    )
    (net (code "53") (name "GND") (class "Default")
      (node (ref "C1") (pin "1") (pinfunction "1_1") (pintype "unspecified"))
      (node (ref "C13") (pin "1") (pinfunction "1_1") (pintype "unspecified"))
      (node (ref "C18") (pin "1") (pinfunction "1_1") (pintype "unspecified"))
      (node (ref "CARD2") (pin "6") (pinfunction "VSS_6") (pintype "unspecified"))
      (node (ref "D2") (pin "1") (pinfunction "1_1") (pintype "unspecified"))
      (node (ref "D2") (pin "2") (pinfunction "2_2") (pintype "unspecified"))
      (node (ref "D6") (pin "2") (pinfunction "2_2") (pintype "unspecified"))
      (node (ref "D7") (pin "2") (pinfunction "2_2") (pintype "unspecified"))
      (node (ref "H1") (pin "8") (pinfunction "8_8") (pintype "input"))
      (node (ref "H2") (pin "11") (pinfunction "11_11") (pintype "input"))
      (node (ref "H2") (pin "13") (pinfunction "13_13") (pintype "input"))
      (node (ref "H3") (pin "12") (pinfunction "12_12") (pintype "input"))
      (node (ref "H4") (pin "17") (pinfunction "17_17") (pintype "input"))
      (node (ref "H4") (pin "22") (pinfunction "22_22") (pintype "input"))
      (node (ref "H4") (pin "27") (pinfunction "27_27") (pintype "input"))
      (node (ref "H4") (pin "5") (pinfunction "5_5") (pintype "input"))
      (node (ref "H5") (pin "1") (pinfunction "1_1") (pintype "unspecified"))
      (node (ref "H5") (pin "2") (pinfunction "2_2") (pintype "unspecified"))
      (node (ref "H5") (pin "3") (pinfunction "3_3") (pintype "unspecified"))
      (node (ref "J1") (pin "7") (pinfunction "7_7") (pintype "unspecified"))
      (node (ref "J11") (pin "18") (pinfunction "18_18") (pintype "input"))
      (node (ref "J11") (pin "21") (pinfunction "21_21") (pintype "input"))
      (node (ref "J11") (pin "28") (pinfunction "28_28") (pintype "input"))
      (node (ref "J11") (pin "6") (pinfunction "6_6") (pintype "input"))
      (node (ref "J13") (pin "1") (pinfunction "1_1") (pintype "unspecified"))
      (node (ref "J13") (pin "10") (pinfunction "10_10") (pintype "unspecified"))
      (node (ref "J13") (pin "11") (pinfunction "11_11") (pintype "unspecified"))
      (node (ref "J13") (pin "12") (pinfunction "12_12") (pintype "unspecified"))
      (node (ref "J13") (pin "13") (pinfunction "13_13") (pintype "unspecified"))
      (node (ref "J13") (pin "14") (pinfunction "14_14") (pintype "unspecified"))
      (node (ref "J13") (pin "15") (pinfunction "15_15") (pintype "unspecified"))
      (node (ref "J13") (pin "16") (pinfunction "16_16") (pintype "unspecified"))
      (node (ref "J13") (pin "17") (pinfunction "17_17") (pintype "unspecified"))
      (node (ref "J13") (pin "18") (pinfunction "18_18") (pintype "unspecified"))
      (node (ref "J13") (pin "19") (pinfunction "19_19") (pintype "unspecified"))
      (node (ref "J13") (pin "2") (pinfunction "2_2") (pintype "unspecified"))
      (node (ref "J13") (pin "20") (pinfunction "20_20") (pintype "unspecified"))
      (node (ref "J13") (pin "3") (pinfunction "3_3") (pintype "unspecified"))
      (node (ref "J13") (pin "4") (pinfunction "4_4") (pintype "unspecified"))
      (node (ref "J13") (pin "5") (pinfunction "5_5") (pintype "unspecified"))
      (node (ref "J13") (pin "6") (pinfunction "6_6") (pintype "unspecified"))
      (node (ref "J13") (pin "7") (pinfunction "7_7") (pintype "unspecified"))
      (node (ref "J13") (pin "8") (pinfunction "8_8") (pintype "unspecified"))
      (node (ref "J13") (pin "9") (pinfunction "9_9") (pintype "unspecified"))
      (node (ref "J3") (pin "12") (pinfunction "12_12") (pintype "input"))
      (node (ref "J3") (pin "14") (pinfunction "14_14") (pintype "input"))
      (node (ref "J4") (pin "1") (pinfunction "1_1") (pintype "unspecified"))
      (node (ref "J4") (pin "10") (pinfunction "10_10") (pintype "unspecified"))
      (node (ref "J4") (pin "11") (pinfunction "11_11") (pintype "unspecified"))
      (node (ref "J4") (pin "12") (pinfunction "12_12") (pintype "unspecified"))
      (node (ref "J4") (pin "13") (pinfunction "13_13") (pintype "unspecified"))
      (node (ref "J4") (pin "14") (pinfunction "14_14") (pintype "unspecified"))
      (node (ref "J4") (pin "15") (pinfunction "15_15") (pintype "unspecified"))
      (node (ref "J4") (pin "16") (pinfunction "16_16") (pintype "unspecified"))
      (node (ref "J4") (pin "17") (pinfunction "17_17") (pintype "unspecified"))
      (node (ref "J4") (pin "18") (pinfunction "18_18") (pintype "unspecified"))
      (node (ref "J4") (pin "19") (pinfunction "19_19") (pintype "unspecified"))
      (node (ref "J4") (pin "2") (pinfunction "2_2") (pintype "unspecified"))
      (node (ref "J4") (pin "20") (pinfunction "20_20") (pintype "unspecified"))
      (node (ref "J4") (pin "3") (pinfunction "3_3") (pintype "unspecified"))
      (node (ref "J4") (pin "4") (pinfunction "4_4") (pintype "unspecified"))
      (node (ref "J4") (pin "5") (pinfunction "5_5") (pintype "unspecified"))
      (node (ref "J4") (pin "6") (pinfunction "6_6") (pintype "unspecified"))
      (node (ref "J4") (pin "7") (pinfunction "7_7") (pintype "unspecified"))
      (node (ref "J4") (pin "8") (pinfunction "8_8") (pintype "unspecified"))
      (node (ref "J4") (pin "9") (pinfunction "9_9") (pintype "unspecified"))
      (node (ref "J7") (pin "11") (pinfunction "11_11") (pintype "input"))
      (node (ref "J9") (pin "1") (pinfunction "1_1") (pintype "unspecified"))
      (node (ref "J9") (pin "2") (pinfunction "2_2") (pintype "unspecified"))
      (node (ref "J9") (pin "3") (pinfunction "3_3") (pintype "unspecified"))
      (node (ref "NRST") (pin "1") (pinfunction "1_1") (pintype "unspecified"))
      (node (ref "NRST") (pin "2") (pinfunction "2_2") (pintype "unspecified"))
      (node (ref "U5") (pin "4") (pinfunction "GND_4") (pintype "unspecified"))
    )
    (net (code "54") (name "IOREF") (class "Default")
      (node (ref "H2") (pin "3") (pinfunction "3_3") (pintype "input"))
      (node (ref "J3") (pin "4") (pinfunction "4_4") (pintype "input"))
    )
    (net (code "55") (name "MISO") (class "Default")
      (node (ref "CN1") (pin "3") (pinfunction "3_3") (pintype "unspecified"))
      (node (ref "CN4") (pin "3") (pinfunction "3_3") (pintype "unspecified"))
      (node (ref "H1") (pin "12") (pinfunction "12_12") (pintype "input"))
      (node (ref "H6") (pin "3") (pinfunction "3_3") (pintype "input"))
      (node (ref "J1") (pin "11") (pinfunction "11_11") (pintype "unspecified"))
      (node (ref "J5") (pin "2") (pinfunction "2_2") (pintype "unspecified"))
      (node (ref "P1") (pin "39") (pinfunction "39_39") (pintype "unspecified"))
      (node (ref "U1") (pin "3") (pinfunction "3_3") (pintype "unspecified"))
    )
    (net (code "56") (name "MISO2") (class "Default")
      (node (ref "CN4") (pin "20") (pinfunction "20_20") (pintype "unspecified"))
      (node (ref "H1") (pin "19") (pinfunction "19_19") (pintype "input"))
      (node (ref "H6") (pin "20") (pinfunction "20_20") (pintype "input"))
      (node (ref "J1") (pin "20") (pinfunction "20_20") (pintype "unspecified"))
      (node (ref "J10") (pin "10") (pinfunction "10_10") (pintype "unspecified"))
      (node (ref "P1") (pin "11") (pinfunction "11_11") (pintype "unspecified"))
      (node (ref "U1") (pin "20") (pinfunction "20_20") (pintype "unspecified"))
    )
    (net (code "57") (name "MOSI") (class "Default")
      (node (ref "CN1") (pin "5") (pinfunction "5_5") (pintype "unspecified"))
      (node (ref "CN4") (pin "5") (pinfunction "5_5") (pintype "unspecified"))
      (node (ref "H1") (pin "14") (pinfunction "14_14") (pintype "input"))
      (node (ref "H6") (pin "5") (pinfunction "5_5") (pintype "input"))
      (node (ref "J1") (pin "13") (pinfunction "13_13") (pintype "unspecified"))
      (node (ref "J5") (pin "3") (pinfunction "3_3") (pintype "unspecified"))
      (node (ref "P1") (pin "38") (pinfunction "38_38") (pintype "unspecified"))
      (node (ref "U1") (pin "5") (pinfunction "5_5") (pintype "unspecified"))
    )
    (net (code "58") (name "MOSI2") (class "Default")
      (node (ref "CN1") (pin "14") (pinfunction "14_14") (pintype "unspecified"))
      (node (ref "CN4") (pin "14") (pinfunction "14_14") (pintype "unspecified"))
      (node (ref "H1") (pin "13") (pinfunction "13_13") (pintype "input"))
      (node (ref "H6") (pin "14") (pinfunction "14_14") (pintype "input"))
      (node (ref "J1") (pin "14") (pinfunction "14_14") (pintype "unspecified"))
      (node (ref "J10") (pin "7") (pinfunction "7_7") (pintype "unspecified"))
      (node (ref "P1") (pin "14") (pinfunction "14_14") (pintype "unspecified"))
      (node (ref "U1") (pin "14") (pinfunction "14_14") (pintype "unspecified"))
    )
    (net (code "59") (name "NRST") (class "Default")
      (node (ref "H2") (pin "5") (pinfunction "5_5") (pintype "input"))
      (node (ref "J3") (pin "6") (pinfunction "6_6") (pintype "input"))
      (node (ref "NRST") (pin "3") (pinfunction "3_3") (pintype "unspecified"))
      (node (ref "NRST") (pin "4") (pinfunction "4_4") (pintype "unspecified"))
    )
    (net (code "60") (name "NSS") (class "Default")
      (node (ref "H1") (pin "9") (pinfunction "9_9") (pintype "input"))
      (node (ref "J1") (pin "10") (pinfunction "10_10") (pintype "unspecified"))
    )
    (net (code "61") (name "NSS2") (class "Default")
      (node (ref "CN4") (pin "18") (pinfunction "18_18") (pintype "unspecified"))
      (node (ref "H1") (pin "17") (pinfunction "17_17") (pintype "input"))
      (node (ref "H6") (pin "18") (pinfunction "18_18") (pintype "input"))
      (node (ref "J1") (pin "18") (pinfunction "18_18") (pintype "unspecified"))
      (node (ref "J10") (pin "9") (pinfunction "9_9") (pintype "unspecified"))
      (node (ref "P1") (pin "12") (pinfunction "12_12") (pintype "unspecified"))
      (node (ref "U1") (pin "18") (pinfunction "18_18") (pintype "unspecified"))
    )
    (net (code "62") (name "Net-(D6-Pad1)") (class "Default")
      (node (ref "D6") (pin "1") (pinfunction "1_1") (pintype "unspecified"))
      (node (ref "R1") (pin "1") (pinfunction "1_1") (pintype "unspecified"))
    )
    (net (code "63") (name "Net-(D7-Pad1)") (class "Default")
      (node (ref "D7") (pin "1") (pinfunction "1_1") (pintype "unspecified"))
      (node (ref "R2") (pin "1") (pinfunction "1_1") (pintype "unspecified"))
    )
    (net (code "64") (name "Net-(J2-Pad1)") (class "Default")
      (node (ref "J2") (pin "1") (pinfunction "1_1") (pintype "unspecified"))
      (node (ref "R24") (pin "2") (pinfunction "2_2") (pintype "unspecified"))
    )
    (net (code "65") (name "QCLK") (class "Default")
      (node (ref "H4") (pin "15") (pinfunction "15_15") (pintype "input"))
      (node (ref "J11") (pin "16") (pinfunction "16_16") (pintype "input"))
      (node (ref "U5") (pin "6") (pinfunction "CLK_6") (pintype "unspecified"))
    )
    (net (code "66") (name "QCS") (class "Default")
      (node (ref "H4") (pin "13") (pinfunction "13_13") (pintype "input"))
      (node (ref "J11") (pin "14") (pinfunction "14_14") (pintype "input"))
      (node (ref "U5") (pin "1") (pinfunction "CS#_1") (pintype "unspecified"))
    )
    (net (code "67") (name "QD0") (class "Default")
      (node (ref "H4") (pin "23") (pinfunction "23_23") (pintype "input"))
      (node (ref "J11") (pin "24") (pinfunction "24_24") (pintype "input"))
      (node (ref "U5") (pin "5") (pinfunction "DI(IO0)_5") (pintype "unspecified"))
    )
    (net (code "68") (name "QD1") (class "Default")
      (node (ref "H4") (pin "21") (pinfunction "21_21") (pintype "input"))
      (node (ref "J11") (pin "22") (pinfunction "22_22") (pintype "input"))
      (node (ref "U5") (pin "2") (pinfunction "DO(IO1)_2") (pintype "unspecified"))
    )
    (net (code "69") (name "QD2") (class "Default")
      (node (ref "H4") (pin "25") (pinfunction "25_25") (pintype "input"))
      (node (ref "J11") (pin "26") (pinfunction "26_26") (pintype "input"))
      (node (ref "U5") (pin "3") (pinfunction "WP#(IO2)_3") (pintype "unspecified"))
    )
    (net (code "70") (name "QD3") (class "Default")
      (node (ref "H4") (pin "19") (pinfunction "19_19") (pintype "input"))
      (node (ref "J11") (pin "20") (pinfunction "20_20") (pintype "input"))
      (node (ref "U5") (pin "7") (pinfunction "HOLD#(IO3)_7") (pintype "unspecified"))
    )
    (net (code "71") (name "SCK") (class "Default")
      (node (ref "CN1") (pin "1") (pinfunction "1_1") (pintype "unspecified"))
      (node (ref "CN4") (pin "1") (pinfunction "1_1") (pintype "unspecified"))
      (node (ref "H1") (pin "10") (pinfunction "10_10") (pintype "input"))
      (node (ref "H6") (pin "1") (pinfunction "1_1") (pintype "input"))
      (node (ref "J1") (pin "9") (pinfunction "9_9") (pintype "unspecified"))
      (node (ref "J5") (pin "1") (pinfunction "1_1") (pintype "unspecified"))
      (node (ref "P1") (pin "40") (pinfunction "40_40") (pintype "unspecified"))
      (node (ref "U1") (pin "1") (pinfunction "1_1") (pintype "unspecified"))
    )
    (net (code "72") (name "SCK2") (class "Default")
      (node (ref "CN1") (pin "16") (pinfunction "16_16") (pintype "unspecified"))
      (node (ref "CN4") (pin "16") (pinfunction "16_16") (pintype "unspecified"))
      (node (ref "H1") (pin "15") (pinfunction "15_15") (pintype "input"))
      (node (ref "H6") (pin "16") (pinfunction "16_16") (pintype "input"))
      (node (ref "J1") (pin "16") (pinfunction "16_16") (pintype "unspecified"))
      (node (ref "J10") (pin "8") (pinfunction "8_8") (pintype "unspecified"))
      (node (ref "P1") (pin "13") (pinfunction "13_13") (pintype "unspecified"))
      (node (ref "U1") (pin "16") (pinfunction "16_16") (pintype "unspecified"))
    )
    (net (code "73") (name "SCL") (class "Default")
      (node (ref "CN1") (pin "2") (pinfunction "2_2") (pintype "unspecified"))
      (node (ref "CN4") (pin "2") (pinfunction "2_2") (pintype "unspecified"))
      (node (ref "H1") (pin "2") (pinfunction "2_2") (pintype "input"))
      (node (ref "H6") (pin "2") (pinfunction "2_2") (pintype "input"))
      (node (ref "J1") (pin "1") (pinfunction "1_1") (pintype "unspecified"))
      (node (ref "J10") (pin "1") (pinfunction "1_1") (pintype "unspecified"))
      (node (ref "P1") (pin "20") (pinfunction "20_20") (pintype "unspecified"))
      (node (ref "U1") (pin "2") (pinfunction "2_2") (pintype "unspecified"))
    )
    (net (code "74") (name "SDA") (class "Default")
      (node (ref "CN1") (pin "4") (pinfunction "4_4") (pintype "unspecified"))
      (node (ref "CN4") (pin "4") (pinfunction "4_4") (pintype "unspecified"))
      (node (ref "H1") (pin "4") (pinfunction "4_4") (pintype "input"))
      (node (ref "H6") (pin "4") (pinfunction "4_4") (pintype "input"))
      (node (ref "J1") (pin "3") (pinfunction "3_3") (pintype "unspecified"))
      (node (ref "J10") (pin "2") (pinfunction "2_2") (pintype "unspecified"))
      (node (ref "P1") (pin "19") (pinfunction "19_19") (pintype "unspecified"))
      (node (ref "U1") (pin "4") (pinfunction "4_4") (pintype "unspecified"))
    )
    (net (code "75") (name "URX") (class "Default")
      (node (ref "H4") (pin "16") (pinfunction "16_16") (pintype "input"))
      (node (ref "J11") (pin "15") (pinfunction "15_15") (pintype "input"))
    )
    (net (code "76") (name "UTX") (class "Default")
      (node (ref "H4") (pin "14") (pinfunction "14_14") (pintype "input"))
      (node (ref "J11") (pin "13") (pinfunction "13_13") (pintype "input"))
    )
    (net (code "77") (name "VIN") (class "Default")
      (node (ref "H2") (pin "15") (pinfunction "15_15") (pintype "input"))
      (node (ref "J3") (pin "16") (pinfunction "16_16") (pintype "input"))
    )
    (net (code "78") (name "unconnected-(CARD2-CD-Pad9)") (class "Default")
      (node (ref "CARD2") (pin "9") (pinfunction "CD_9") (pintype "unspecified+no_connect"))
    )
    (net (code "79") (name "unconnected-(CARD2-SHELL-Pad10)") (class "Default")
      (node (ref "CARD2") (pin "10") (pinfunction "SHELL_10") (pintype "unspecified+no_connect"))
    )
    (net (code "80") (name "unconnected-(CARD2-SHELL-Pad11)") (class "Default")
      (node (ref "CARD2") (pin "11") (pinfunction "SHELL_11") (pintype "unspecified+no_connect"))
    )
    (net (code "81") (name "unconnected-(CARD2-SHELL-Pad12)") (class "Default")
      (node (ref "CARD2") (pin "12") (pinfunction "SHELL_12") (pintype "unspecified+no_connect"))
    )
    (net (code "82") (name "unconnected-(CARD2-SHELL-Pad13)") (class "Default")
      (node (ref "CARD2") (pin "13") (pinfunction "SHELL_13") (pintype "unspecified+no_connect"))
    )
    (net (code "83") (name "unconnected-(CN1-Pad17)") (class "Default")
      (node (ref "CN1") (pin "17") (pinfunction "17_17") (pintype "unspecified"))
    )
    (net (code "84") (name "unconnected-(CN1-Pad18)") (class "Default")
      (node (ref "CN1") (pin "18") (pinfunction "18_18") (pintype "unspecified"))
    )
    (net (code "85") (name "unconnected-(CN1-Pad19)") (class "Default")
      (node (ref "CN1") (pin "19") (pinfunction "19_19") (pintype "unspecified"))
    )
    (net (code "86") (name "unconnected-(CN1-Pad20)") (class "Default")
      (node (ref "CN1") (pin "20") (pinfunction "20_20") (pintype "unspecified"))
    )
    (net (code "87") (name "unconnected-(CN4-Pad31)") (class "Default")
      (node (ref "CN4") (pin "31") (pinfunction "31_31") (pintype "unspecified"))
    )
    (net (code "88") (name "unconnected-(CN4-Pad32)") (class "Default")
      (node (ref "CN4") (pin "32") (pinfunction "32_32") (pintype "unspecified"))
    )
    (net (code "89") (name "unconnected-(CN4-Pad33)") (class "Default")
      (node (ref "CN4") (pin "33") (pinfunction "33_33") (pintype "unspecified"))
    )
    (net (code "90") (name "unconnected-(CN4-Pad34)") (class "Default")
      (node (ref "CN4") (pin "34") (pinfunction "34_34") (pintype "unspecified"))
    )
    (net (code "91") (name "unconnected-(H2-Pad1)") (class "Default")
      (node (ref "H2") (pin "1") (pinfunction "1_1") (pintype "input"))
    )
    (net (code "92") (name "unconnected-(J3-Pad2)") (class "Default")
      (node (ref "J3") (pin "2") (pinfunction "2_2") (pintype "input"))
    )
    (net (code "93") (name "unconnected-(P1-Pad41)") (class "Default")
      (node (ref "P1") (pin "41") (pinfunction "41_41") (pintype "unspecified"))
    )
    (net (code "94") (name "unconnected-(P1-Pad42)") (class "Default")
      (node (ref "P1") (pin "42") (pinfunction "42_42") (pintype "unspecified"))
    )
    (net (code "95") (name "unconnected-(U1-Pad25)") (class "Default")
      (node (ref "U1") (pin "25") (pinfunction "25_25") (pintype "unspecified"))
    )
    (net (code "96") (name "unconnected-(U1-Pad26)") (class "Default")
      (node (ref "U1") (pin "26") (pinfunction "26_26") (pintype "unspecified"))
    )
    (net (code "97") (name "unconnected-(U1-Pad27)") (class "Default")
      (node (ref "U1") (pin "27") (pinfunction "27_27") (pintype "unspecified"))
    )
    (net (code "98") (name "unconnected-(U1-Pad28)") (class "Default")
      (node (ref "U1") (pin "28") (pinfunction "28_28") (pintype "unspecified"))
    )
  )
)
